# SparkFun_TMP102_Qwiic.net
KiCad netlist of a schematic drawn in EAGLE
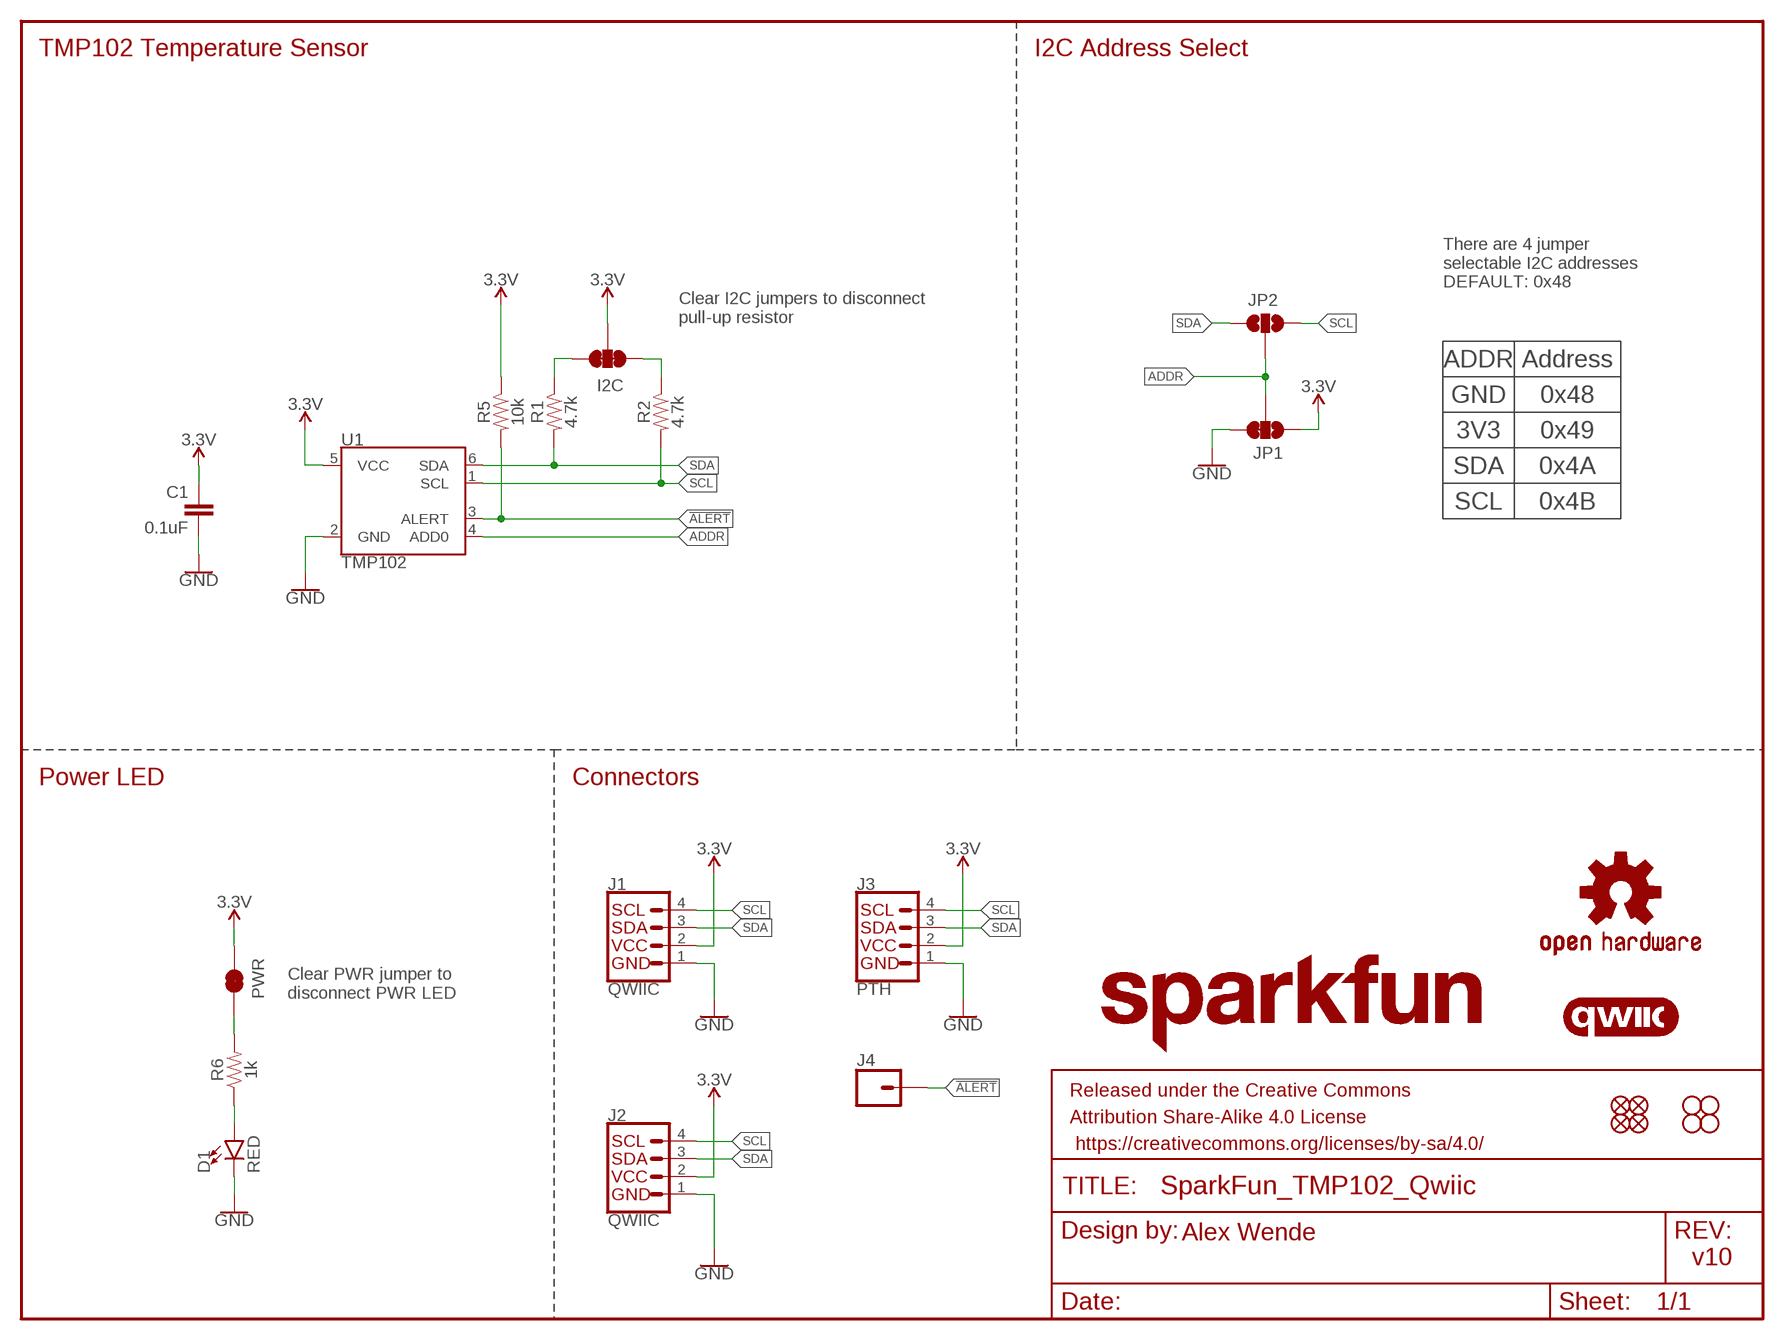
[diagram p0: schematic, sheet 1]

(export (version "E")
  (design (tool "Eeschema 10.0.6"))
  (components
    (comp (ref "C1")
      (value "0.1uF")
      (footprint "eagle-import:0603")
      (libsource (lib "eagle-import") (part "0.1UF-0603-25V-(+80/-20%)"))
    )
    (comp (ref "D1")
      (value "RED")
      (footprint "eagle-import:LED-0603")
      (libsource (lib "eagle-import") (part "LED-RED0603"))
    )
    (comp (ref "FD1")
      (value "FIDUCIALUFIDUCIAL")
      (footprint "eagle-import:FIDUCIAL-MICRO")
      (libsource (lib "eagle-import") (part "FIDUCIALUFIDUCIAL"))
    )
    (comp (ref "FD2")
      (value "FIDUCIALUFIDUCIAL")
      (footprint "eagle-import:FIDUCIAL-MICRO")
      (libsource (lib "eagle-import") (part "FIDUCIALUFIDUCIAL"))
    )
    (comp (ref "FD3")
      (value "FIDUCIALUFIDUCIAL")
      (footprint "eagle-import:FIDUCIAL-MICRO")
      (libsource (lib "eagle-import") (part "FIDUCIALUFIDUCIAL"))
    )
    (comp (ref "FD4")
      (value "FIDUCIALUFIDUCIAL")
      (footprint "eagle-import:FIDUCIAL-MICRO")
      (libsource (lib "eagle-import") (part "FIDUCIALUFIDUCIAL"))
    )
    (comp (ref "FRAME1")
      (value "FRAME-LETTER")
      (footprint "eagle-import:CREATIVE_COMMONS")
      (libsource (lib "eagle-import") (part "FRAME-LETTER"))
    )
    (comp (ref "H1")
      (value "STAND-OFF")
      (footprint "eagle-import:STAND-OFF")
      (libsource (lib "eagle-import") (part "STAND-OFF"))
    )
    (comp (ref "H2")
      (value "STAND-OFF")
      (footprint "eagle-import:STAND-OFF")
      (libsource (lib "eagle-import") (part "STAND-OFF"))
    )
    (comp (ref "H3")
      (value "STAND-OFF")
      (footprint "eagle-import:STAND-OFF")
      (libsource (lib "eagle-import") (part "STAND-OFF"))
    )
    (comp (ref "H4")
      (value "STAND-OFF")
      (footprint "eagle-import:STAND-OFF")
      (libsource (lib "eagle-import") (part "STAND-OFF"))
    )
    (comp (ref "J1")
      (value "QWIIC")
      (footprint "eagle-import:JST04_1MM_RA")
      (libsource (lib "eagle-import") (part "QWIIC_CONNECTORJS-1MM"))
    )
    (comp (ref "J2")
      (value "QWIIC")
      (footprint "eagle-import:JST04_1MM_RA")
      (libsource (lib "eagle-import") (part "QWIIC_CONNECTORJS-1MM"))
    )
    (comp (ref "J3")
      (value "PTH")
      (footprint "eagle-import:1X04_NO_SILK")
      (libsource (lib "eagle-import") (part "I2C_STANDARD_NO_SILK"))
    )
    (comp (ref "J4")
      (value "CONN_01PTH_NO_SILK_YES_STOP")
      (footprint "eagle-import:1X01_NO_SILK")
      (libsource (lib "eagle-import") (part "CONN_01PTH_NO_SILK_YES_STOP"))
    )
    (comp (ref "JP1")
      (value "JUMPER-SMT_3_1-NC_TRACE_NO-SILK")
      (footprint "eagle-import:SMT-JUMPER_3_1-NC_TRACE_NO-SILK")
      (libsource (lib "eagle-import") (part "JUMPER-SMT_3_1-NC_TRACE_NO-SILK"))
    )
    (comp (ref "JP2")
      (value "JUMPER-SMT_3_NO_NO-SILK")
      (footprint "eagle-import:SMT-JUMPER_3_NO_NO-SILK")
      (libsource (lib "eagle-import") (part "JUMPER-SMT_3_NO_NO-SILK"))
    )
    (comp (ref "JP3")
      (value "I2C")
      (footprint "eagle-import:SMT-JUMPER_3_2-NC_TRACE_SILK")
      (libsource (lib "eagle-import") (part "JUMPER-SMT_3_2-NC_TRACE_SILK"))
    )
    (comp (ref "JP4")
      (value "PWR")
      (footprint "eagle-import:SMT-JUMPER_2_NC_TRACE_SILK")
      (libsource (lib "eagle-import") (part "JUMPER-SMT_2_NC_TRACE_SILK"))
    )
    (comp (ref "LOGO1")
      (value "SFE_LOGO_NAME.1_INCH")
      (footprint "eagle-import:SFE_LOGO_NAME_.1")
      (libsource (lib "eagle-import") (part "SFE_LOGO_NAME.1_INCH"))
    )
    (comp (ref "LOGO2")
      (value "QWIIC_LOGO_5MM")
      (footprint "eagle-import:QWIIC_5MM")
      (libsource (lib "eagle-import") (part "QWIIC_LOGO_5MM"))
    )
    (comp (ref "LOGO3")
      (value "OSHW-LOGOS")
      (footprint "eagle-import:OSHW-LOGO-S")
      (libsource (lib "eagle-import") (part "OSHW-LOGOS"))
    )
    (comp (ref "R1")
      (value "4.7k")
      (footprint "eagle-import:0603")
      (libsource (lib "eagle-import") (part "4.7KOHM-0603-1/10W-1%"))
    )
    (comp (ref "R2")
      (value "4.7k")
      (footprint "eagle-import:0603")
      (libsource (lib "eagle-import") (part "4.7KOHM-0603-1/10W-1%"))
    )
    (comp (ref "R5")
      (value "10k")
      (footprint "eagle-import:0603")
      (libsource (lib "eagle-import") (part "10KOHM-0603-1/10W-1%"))
    )
    (comp (ref "R6")
      (value "1k")
      (footprint "eagle-import:0603")
      (libsource (lib "eagle-import") (part "1KOHM-0603-1/10W-1%"))
    )
    (comp (ref "U1")
      (value "TMP102")
      (footprint "eagle-import:SOT563")
      (libsource (lib "eagle-import") (part "TMP102"))
    )
  )
  (nets
    (net (code "1") (name "/~{ALERT}") (class "Default")
      (node (ref "J4") (pin "1") (pinfunction "1_1") (pintype "passive"))
      (node (ref "R5") (pin "2") (pinfunction "2_2") (pintype "passive"))
      (node (ref "U1") (pin "3") (pinfunction "ALERT_3") (pintype "bidirectional"))
    )
    (net (code "2") (name "3.3V") (class "Default")
      (node (ref "C1") (pin "1") (pinfunction "1_1") (pintype "passive"))
      (node (ref "J1") (pin "2") (pinfunction "2_2") (pintype "power_in"))
      (node (ref "J2") (pin "2") (pinfunction "2_2") (pintype "power_in"))
      (node (ref "J3") (pin "2") (pinfunction "2_2") (pintype "power_in"))
      (node (ref "JP1") (pin "1") (pinfunction "1_1") (pintype "passive"))
      (node (ref "JP3") (pin "2") (pinfunction "2_2") (pintype "passive"))
      (node (ref "JP4") (pin "2") (pinfunction "2_2") (pintype "passive"))
      (node (ref "R5") (pin "1") (pinfunction "1_1") (pintype "passive"))
      (node (ref "U1") (pin "5") (pinfunction "VCC_5") (pintype "bidirectional"))
    )
    (net (code "3") (name "ADDR") (class "Default")
      (node (ref "JP1") (pin "2") (pinfunction "2_2") (pintype "passive"))
      (node (ref "JP2") (pin "2") (pinfunction "2_2") (pintype "passive"))
      (node (ref "U1") (pin "4") (pinfunction "ADD0_4") (pintype "bidirectional"))
    )
    (net (code "4") (name "GND") (class "Default")
      (node (ref "C1") (pin "2") (pinfunction "2_2") (pintype "passive"))
      (node (ref "D1") (pin "C") (pinfunction "C_C") (pintype "passive"))
      (node (ref "J1") (pin "1") (pinfunction "1_1") (pintype "power_in"))
      (node (ref "J2") (pin "1") (pinfunction "1_1") (pintype "power_in"))
      (node (ref "J3") (pin "1") (pinfunction "1_1") (pintype "power_in"))
      (node (ref "JP1") (pin "3") (pinfunction "3_3") (pintype "passive"))
      (node (ref "U1") (pin "2") (pinfunction "GND_2") (pintype "bidirectional"))
    )
    (net (code "5") (name "Net-(D1-PadA)") (class "Default")
      (node (ref "D1") (pin "A") (pinfunction "A_A") (pintype "passive"))
      (node (ref "R6") (pin "1") (pinfunction "1_1") (pintype "passive"))
    )
    (net (code "6") (name "Net-(JP3-Pad1)") (class "Default")
      (node (ref "JP3") (pin "1") (pinfunction "1_1") (pintype "passive"))
      (node (ref "R2") (pin "1") (pinfunction "1_1") (pintype "passive"))
    )
    (net (code "7") (name "Net-(JP3-Pad3)") (class "Default")
      (node (ref "JP3") (pin "3") (pinfunction "3_3") (pintype "passive"))
      (node (ref "R1") (pin "1") (pinfunction "1_1") (pintype "passive"))
    )
    (net (code "8") (name "Net-(JP4-Pad1)") (class "Default")
      (node (ref "JP4") (pin "1") (pinfunction "1_1") (pintype "passive"))
      (node (ref "R6") (pin "2") (pinfunction "2_2") (pintype "passive"))
    )
    (net (code "9") (name "SCL") (class "Default")
      (node (ref "J1") (pin "4") (pinfunction "4_4") (pintype "passive"))
      (node (ref "J2") (pin "4") (pinfunction "4_4") (pintype "passive"))
      (node (ref "J3") (pin "4") (pinfunction "4_4") (pintype "passive"))
      (node (ref "JP2") (pin "1") (pinfunction "1_1") (pintype "passive"))
      (node (ref "R2") (pin "2") (pinfunction "2_2") (pintype "passive"))
      (node (ref "U1") (pin "1") (pinfunction "SCL_1") (pintype "bidirectional"))
    )
    (net (code "10") (name "SDA") (class "Default")
      (node (ref "J1") (pin "3") (pinfunction "3_3") (pintype "passive"))
      (node (ref "J2") (pin "3") (pinfunction "3_3") (pintype "passive"))
      (node (ref "J3") (pin "3") (pinfunction "3_3") (pintype "passive"))
      (node (ref "JP2") (pin "3") (pinfunction "3_3") (pintype "passive"))
      (node (ref "R1") (pin "2") (pinfunction "2_2") (pintype "passive"))
      (node (ref "U1") (pin "6") (pinfunction "SDA_6") (pintype "bidirectional"))
    )
  )
)
